# NYclock2.net
KiCad netlist of a schematic drawn in EAGLE
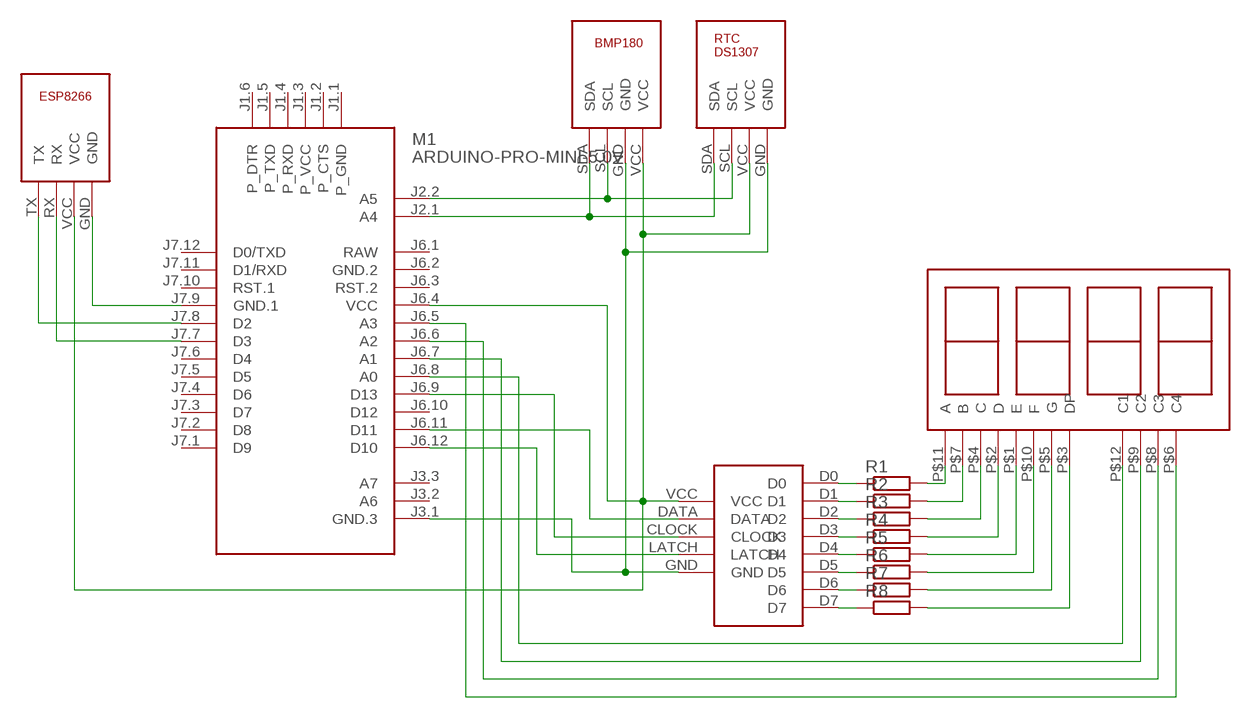
[diagram p0: schematic, sheet 1]

(export (version "E")
  (design (tool "Eeschema 10.0.6"))
  (components
    (comp (ref "1")
      (value "SHIFTREG")
      (footprint "eagle-import:SHIFTREG")
      (libsource (lib "eagle-import") (part "SHIFTREG"))
    )
    (comp (ref "M1")
      (value "ARDUINO-PRO-MINI-5.0V")
      (footprint "eagle-import:ARDUINO-PRO-MINI")
      (libsource (lib "eagle-import") (part "ARDUINO-PRO-MINI-5.0V"))
    )
    (comp (ref "R1")
      (value "R-EU_0204/2V")
      (footprint "eagle-import:0204V")
      (libsource (lib "eagle-import") (part "R-EU_0204/2V"))
    )
    (comp (ref "R2")
      (value "R-EU_0204/2V")
      (footprint "eagle-import:0204V")
      (libsource (lib "eagle-import") (part "R-EU_0204/2V"))
    )
    (comp (ref "R3")
      (value "R-EU_0204/2V")
      (footprint "eagle-import:0204V")
      (libsource (lib "eagle-import") (part "R-EU_0204/2V"))
    )
    (comp (ref "R4")
      (value "R-EU_0204/2V")
      (footprint "eagle-import:0204V")
      (libsource (lib "eagle-import") (part "R-EU_0204/2V"))
    )
    (comp (ref "R5")
      (value "R-EU_0204/2V")
      (footprint "eagle-import:0204V")
      (libsource (lib "eagle-import") (part "R-EU_0204/2V"))
    )
    (comp (ref "R6")
      (value "R-EU_0204/2V")
      (footprint "eagle-import:0204V")
      (libsource (lib "eagle-import") (part "R-EU_0204/2V"))
    )
    (comp (ref "R7")
      (value "R-EU_0204/2V")
      (footprint "eagle-import:0204V")
      (libsource (lib "eagle-import") (part "R-EU_0204/2V"))
    )
    (comp (ref "R8")
      (value "R-EU_0204/2V")
      (footprint "eagle-import:0204V")
      (libsource (lib "eagle-import") (part "R-EU_0204/2V"))
    )
    (comp (ref "U$1")
      (value "BMP180")
      (footprint "eagle-import:BMP180")
      (libsource (lib "eagle-import") (part "BMP180"))
    )
    (comp (ref "U$2")
      (value "7SEGDIGITS")
      (footprint "eagle-import:7SEGDIGITS")
      (libsource (lib "eagle-import") (part "7SEGDIGITS"))
    )
    (comp (ref "U$3")
      (value "ESP8266")
      (footprint "eagle-import:ESP8266")
      (libsource (lib "eagle-import") (part "ESP8266"))
    )
    (comp (ref "U$4")
      (value "RTC")
      (footprint "eagle-import:RTC")
      (libsource (lib "eagle-import") (part "RTC"))
    )
  )
  (nets
    (net (code "1") (name "/GND.2") (class "Default")
      (node (ref "M1") (pin "J6.2") (pinfunction "GND.2_J6.2") (pintype "power_in"))
    )
    (net (code "2") (name "/RAW") (class "Default")
      (node (ref "M1") (pin "J6.1") (pinfunction "RAW_J6.1") (pintype "power_in"))
    )
    (net (code "3") (name "Net-(1-PadD0)") (class "Default")
      (node (ref "1") (pin "D0") (pinfunction "D0_D0") (pintype "bidirectional"))
      (node (ref "R1") (pin "1") (pinfunction "1_1") (pintype "passive"))
    )
    (net (code "4") (name "Net-(1-PadD1)") (class "Default")
      (node (ref "1") (pin "D1") (pinfunction "D1_D1") (pintype "bidirectional"))
      (node (ref "R2") (pin "1") (pinfunction "1_1") (pintype "passive"))
    )
    (net (code "5") (name "Net-(1-PadD2)") (class "Default")
      (node (ref "1") (pin "D2") (pinfunction "D2_D2") (pintype "bidirectional"))
      (node (ref "R3") (pin "1") (pinfunction "1_1") (pintype "passive"))
    )
    (net (code "6") (name "Net-(1-PadD3)") (class "Default")
      (node (ref "1") (pin "D3") (pinfunction "D3_D3") (pintype "bidirectional"))
      (node (ref "R4") (pin "1") (pinfunction "1_1") (pintype "passive"))
    )
    (net (code "7") (name "Net-(1-PadD4)") (class "Default")
      (node (ref "1") (pin "D4") (pinfunction "D4_D4") (pintype "bidirectional"))
      (node (ref "R5") (pin "1") (pinfunction "1_1") (pintype "passive"))
    )
    (net (code "8") (name "Net-(1-PadD5)") (class "Default")
      (node (ref "1") (pin "D5") (pinfunction "D5_D5") (pintype "bidirectional"))
      (node (ref "R6") (pin "1") (pinfunction "1_1") (pintype "passive"))
    )
    (net (code "9") (name "Net-(1-PadD6)") (class "Default")
      (node (ref "1") (pin "D6") (pinfunction "D6_D6") (pintype "bidirectional"))
      (node (ref "R7") (pin "1") (pinfunction "1_1") (pintype "passive"))
    )
    (net (code "10") (name "Net-(1-PadD7)") (class "Default")
      (node (ref "1") (pin "D7") (pinfunction "D7_D7") (pintype "bidirectional"))
      (node (ref "R8") (pin "1") (pinfunction "1_1") (pintype "passive"))
    )
    (net (code "11") (name "Net-(M1-A0)") (class "Default")
      (node (ref "M1") (pin "J6.8") (pinfunction "A0_J6.8") (pintype "bidirectional"))
      (node (ref "U$2") (pin "P$12") (pinfunction "C1_P$12") (pintype "bidirectional"))
    )
    (net (code "12") (name "Net-(M1-A1)") (class "Default")
      (node (ref "M1") (pin "J6.7") (pinfunction "A1_J6.7") (pintype "bidirectional"))
      (node (ref "U$2") (pin "P$9") (pinfunction "C2_P$9") (pintype "bidirectional"))
    )
    (net (code "13") (name "Net-(M1-A2)") (class "Default")
      (node (ref "M1") (pin "J6.6") (pinfunction "A2_J6.6") (pintype "bidirectional"))
      (node (ref "U$2") (pin "P$8") (pinfunction "C3_P$8") (pintype "bidirectional"))
    )
    (net (code "14") (name "Net-(M1-A3)") (class "Default")
      (node (ref "M1") (pin "J6.5") (pinfunction "A3_J6.5") (pintype "bidirectional"))
      (node (ref "U$2") (pin "P$6") (pinfunction "C4_P$6") (pintype "bidirectional"))
    )
    (net (code "15") (name "Net-(M1-A4)") (class "Default")
      (node (ref "M1") (pin "J2.1") (pinfunction "A4_J2.1") (pintype "bidirectional"))
      (node (ref "U$1") (pin "SDA") (pinfunction "SDA_SDA") (pintype "bidirectional"))
      (node (ref "U$4") (pin "SDA") (pinfunction "SDA_SDA") (pintype "bidirectional"))
    )
    (net (code "16") (name "Net-(M1-A5)") (class "Default")
      (node (ref "M1") (pin "J2.2") (pinfunction "A5_J2.2") (pintype "bidirectional"))
      (node (ref "U$1") (pin "SCL") (pinfunction "SCL_SCL") (pintype "bidirectional"))
      (node (ref "U$4") (pin "SCL") (pinfunction "SCL_SCL") (pintype "bidirectional"))
    )
    (net (code "17") (name "Net-(M1-D2)") (class "Default")
      (node (ref "M1") (pin "J7.8") (pinfunction "D2_J7.8") (pintype "bidirectional"))
      (node (ref "U$3") (pin "TX") (pinfunction "TX_TX") (pintype "bidirectional"))
    )
    (net (code "18") (name "Net-(M1-D3)") (class "Default")
      (node (ref "M1") (pin "J7.7") (pinfunction "D3_J7.7") (pintype "bidirectional"))
      (node (ref "U$3") (pin "RX") (pinfunction "RX_RX") (pintype "bidirectional"))
    )
    (net (code "19") (name "Net-(M1-D10)") (class "Default")
      (node (ref "1") (pin "LATCH") (pinfunction "LATCH_LATCH") (pintype "bidirectional"))
      (node (ref "M1") (pin "J6.12") (pinfunction "D10_J6.12") (pintype "bidirectional"))
    )
    (net (code "20") (name "Net-(M1-D11)") (class "Default")
      (node (ref "1") (pin "DATA") (pinfunction "DATA_DATA") (pintype "bidirectional"))
      (node (ref "M1") (pin "J6.11") (pinfunction "D11_J6.11") (pintype "bidirectional"))
    )
    (net (code "21") (name "Net-(M1-D13)") (class "Default")
      (node (ref "1") (pin "CLOCK") (pinfunction "CLOCK_CLOCK") (pintype "bidirectional"))
      (node (ref "M1") (pin "J6.9") (pinfunction "D13_J6.9") (pintype "bidirectional"))
    )
    (net (code "22") (name "Net-(M1-GND.1)") (class "Default")
      (node (ref "M1") (pin "J7.9") (pinfunction "GND.1_J7.9") (pintype "power_in"))
      (node (ref "U$3") (pin "GND") (pinfunction "GND_GND") (pintype "bidirectional"))
    )
    (net (code "23") (name "Net-(M1-GND.3)") (class "Default")
      (node (ref "1") (pin "GND") (pinfunction "GND_GND") (pintype "bidirectional"))
      (node (ref "M1") (pin "J3.1") (pinfunction "GND.3_J3.1") (pintype "bidirectional"))
      (node (ref "U$1") (pin "GND") (pinfunction "GND_GND") (pintype "bidirectional"))
      (node (ref "U$4") (pin "GND") (pinfunction "GND_GND") (pintype "bidirectional"))
    )
    (net (code "24") (name "Net-(M1-VCC)") (class "Default")
      (node (ref "1") (pin "VCC") (pinfunction "VCC_VCC") (pintype "bidirectional"))
      (node (ref "M1") (pin "J6.4") (pinfunction "VCC_J6.4") (pintype "power_in"))
      (node (ref "U$1") (pin "VCC") (pinfunction "VCC_VCC") (pintype "bidirectional"))
      (node (ref "U$3") (pin "VCC") (pinfunction "VCC_VCC") (pintype "bidirectional"))
      (node (ref "U$4") (pin "VCC") (pinfunction "VCC_VCC") (pintype "bidirectional"))
    )
    (net (code "25") (name "Net-(U$2-A)") (class "Default")
      (node (ref "R1") (pin "2") (pinfunction "2_2") (pintype "passive"))
      (node (ref "U$2") (pin "P$11") (pinfunction "A_P$11") (pintype "bidirectional"))
    )
    (net (code "26") (name "Net-(U$2-B)") (class "Default")
      (node (ref "R2") (pin "2") (pinfunction "2_2") (pintype "passive"))
      (node (ref "U$2") (pin "P$7") (pinfunction "B_P$7") (pintype "bidirectional"))
    )
    (net (code "27") (name "Net-(U$2-C)") (class "Default")
      (node (ref "R3") (pin "2") (pinfunction "2_2") (pintype "passive"))
      (node (ref "U$2") (pin "P$4") (pinfunction "C_P$4") (pintype "bidirectional"))
    )
    (net (code "28") (name "Net-(U$2-D)") (class "Default")
      (node (ref "R4") (pin "2") (pinfunction "2_2") (pintype "passive"))
      (node (ref "U$2") (pin "P$2") (pinfunction "D_P$2") (pintype "bidirectional"))
    )
    (net (code "29") (name "Net-(U$2-DP)") (class "Default")
      (node (ref "R8") (pin "2") (pinfunction "2_2") (pintype "passive"))
      (node (ref "U$2") (pin "P$3") (pinfunction "DP_P$3") (pintype "bidirectional"))
    )
    (net (code "30") (name "Net-(U$2-E)") (class "Default")
      (node (ref "R5") (pin "2") (pinfunction "2_2") (pintype "passive"))
      (node (ref "U$2") (pin "P$1") (pinfunction "E_P$1") (pintype "bidirectional"))
    )
    (net (code "31") (name "Net-(U$2-F)") (class "Default")
      (node (ref "R6") (pin "2") (pinfunction "2_2") (pintype "passive"))
      (node (ref "U$2") (pin "P$10") (pinfunction "F_P$10") (pintype "bidirectional"))
    )
    (net (code "32") (name "Net-(U$2-G)") (class "Default")
      (node (ref "R7") (pin "2") (pinfunction "2_2") (pintype "passive"))
      (node (ref "U$2") (pin "P$5") (pinfunction "G_P$5") (pintype "bidirectional"))
    )
    (net (code "33") (name "unconnected-(M1-A6-PadJ3.2)") (class "Default")
      (node (ref "M1") (pin "J3.2") (pinfunction "A6_J3.2") (pintype "bidirectional"))
    )
    (net (code "34") (name "unconnected-(M1-A7-PadJ3.3)") (class "Default")
      (node (ref "M1") (pin "J3.3") (pinfunction "A7_J3.3") (pintype "bidirectional"))
    )
    (net (code "35") (name "unconnected-(M1-D0{slash}TXD-PadJ7.12)") (class "Default")
      (node (ref "M1") (pin "J7.12") (pinfunction "D0/TXD_J7.12") (pintype "bidirectional"))
    )
    (net (code "36") (name "unconnected-(M1-D1{slash}RXD-PadJ7.11)") (class "Default")
      (node (ref "M1") (pin "J7.11") (pinfunction "D1/RXD_J7.11") (pintype "bidirectional"))
    )
    (net (code "37") (name "unconnected-(M1-D4-PadJ7.6)") (class "Default")
      (node (ref "M1") (pin "J7.6") (pinfunction "D4_J7.6") (pintype "bidirectional"))
    )
    (net (code "38") (name "unconnected-(M1-D5-PadJ7.5)") (class "Default")
      (node (ref "M1") (pin "J7.5") (pinfunction "D5_J7.5") (pintype "bidirectional"))
    )
    (net (code "39") (name "unconnected-(M1-D6-PadJ7.4)") (class "Default")
      (node (ref "M1") (pin "J7.4") (pinfunction "D6_J7.4") (pintype "bidirectional"))
    )
    (net (code "40") (name "unconnected-(M1-D7-PadJ7.3)") (class "Default")
      (node (ref "M1") (pin "J7.3") (pinfunction "D7_J7.3") (pintype "bidirectional"))
    )
    (net (code "41") (name "unconnected-(M1-D8-PadJ7.2)") (class "Default")
      (node (ref "M1") (pin "J7.2") (pinfunction "D8_J7.2") (pintype "bidirectional"))
    )
    (net (code "42") (name "unconnected-(M1-D9-PadJ7.1)") (class "Default")
      (node (ref "M1") (pin "J7.1") (pinfunction "D9_J7.1") (pintype "bidirectional"))
    )
    (net (code "43") (name "unconnected-(M1-D12-PadJ6.10)") (class "Default")
      (node (ref "M1") (pin "J6.10") (pinfunction "D12_J6.10") (pintype "bidirectional"))
    )
    (net (code "44") (name "unconnected-(M1-P_CTS-PadJ1.2)") (class "Default")
      (node (ref "M1") (pin "J1.2") (pinfunction "P_CTS_J1.2") (pintype "bidirectional"))
    )
    (net (code "45") (name "unconnected-(M1-P_DTR-PadJ1.6)") (class "Default")
      (node (ref "M1") (pin "J1.6") (pinfunction "P_DTR_J1.6") (pintype "bidirectional"))
    )
    (net (code "46") (name "unconnected-(M1-P_GND-PadJ1.1)") (class "Default")
      (node (ref "M1") (pin "J1.1") (pinfunction "P_GND_J1.1") (pintype "bidirectional"))
    )
    (net (code "47") (name "unconnected-(M1-P_RXD-PadJ1.4)") (class "Default")
      (node (ref "M1") (pin "J1.4") (pinfunction "P_RXD_J1.4") (pintype "bidirectional"))
    )
    (net (code "48") (name "unconnected-(M1-P_TXD-PadJ1.5)") (class "Default")
      (node (ref "M1") (pin "J1.5") (pinfunction "P_TXD_J1.5") (pintype "bidirectional"))
    )
    (net (code "49") (name "unconnected-(M1-P_VCC-PadJ1.3)") (class "Default")
      (node (ref "M1") (pin "J1.3") (pinfunction "P_VCC_J1.3") (pintype "bidirectional"))
    )
    (net (code "50") (name "unconnected-(M1-RST.1-PadJ7.10)") (class "Default")
      (node (ref "M1") (pin "J7.10") (pinfunction "RST.1_J7.10") (pintype "bidirectional"))
    )
    (net (code "51") (name "unconnected-(M1-RST.2-PadJ6.3)") (class "Default")
      (node (ref "M1") (pin "J6.3") (pinfunction "RST.2_J6.3") (pintype "bidirectional"))
    )
  )
)
